# Temperature.net
KiCad netlist of a schematic drawn in Altium Designer
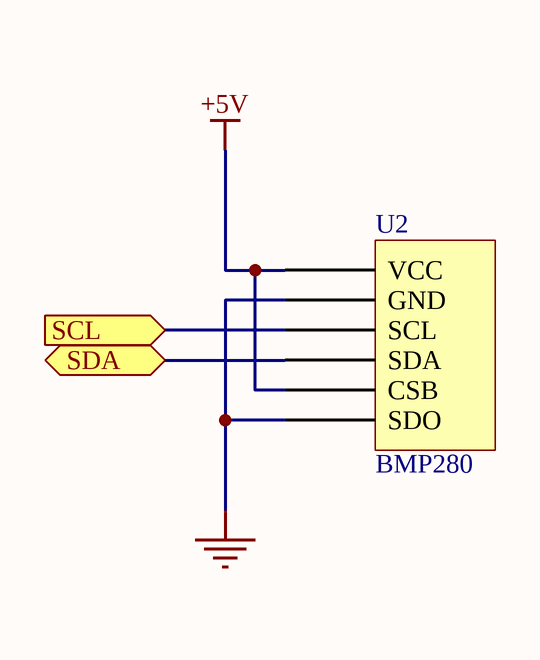
[diagram p0: Temperature.SchDoc]

(export (version "E")
  (design (tool "Eeschema 10.0.6"))
  (components
    (comp (ref "U2")
      (value "BMP280")
      (description "Temperature")
      (libsource (lib "Components") (part "BMP280"))
    )
  )
  (nets
    (net (code "1") (name "+5V") (class "Default")
      (node (ref "U2") (pin "CSB") (pinfunction "CSB_CSB") (pintype "power_in"))
      (node (ref "U2") (pin "VCC") (pinfunction "VCC_VCC") (pintype "power_in"))
    )
    (net (code "2") (name "/SCL") (class "Default")
      (node (ref "U2") (pin "SCL") (pinfunction "SCL_SCL") (pintype "open_collector"))
    )
    (net (code "3") (name "/SDA") (class "Default")
      (node (ref "U2") (pin "SDA") (pinfunction "SDA_SDA") (pintype "open_collector"))
    )
    (net (code "4") (name "GND") (class "Default")
      (node (ref "U2") (pin "GND") (pinfunction "GND_GND") (pintype "power_in"))
      (node (ref "U2") (pin "SDO") (pinfunction "SDO_SDO") (pintype "power_in"))
    )
  )
)
